# SoC_pwr_2.net
KiCad netlist of a schematic drawn in Altium Designer
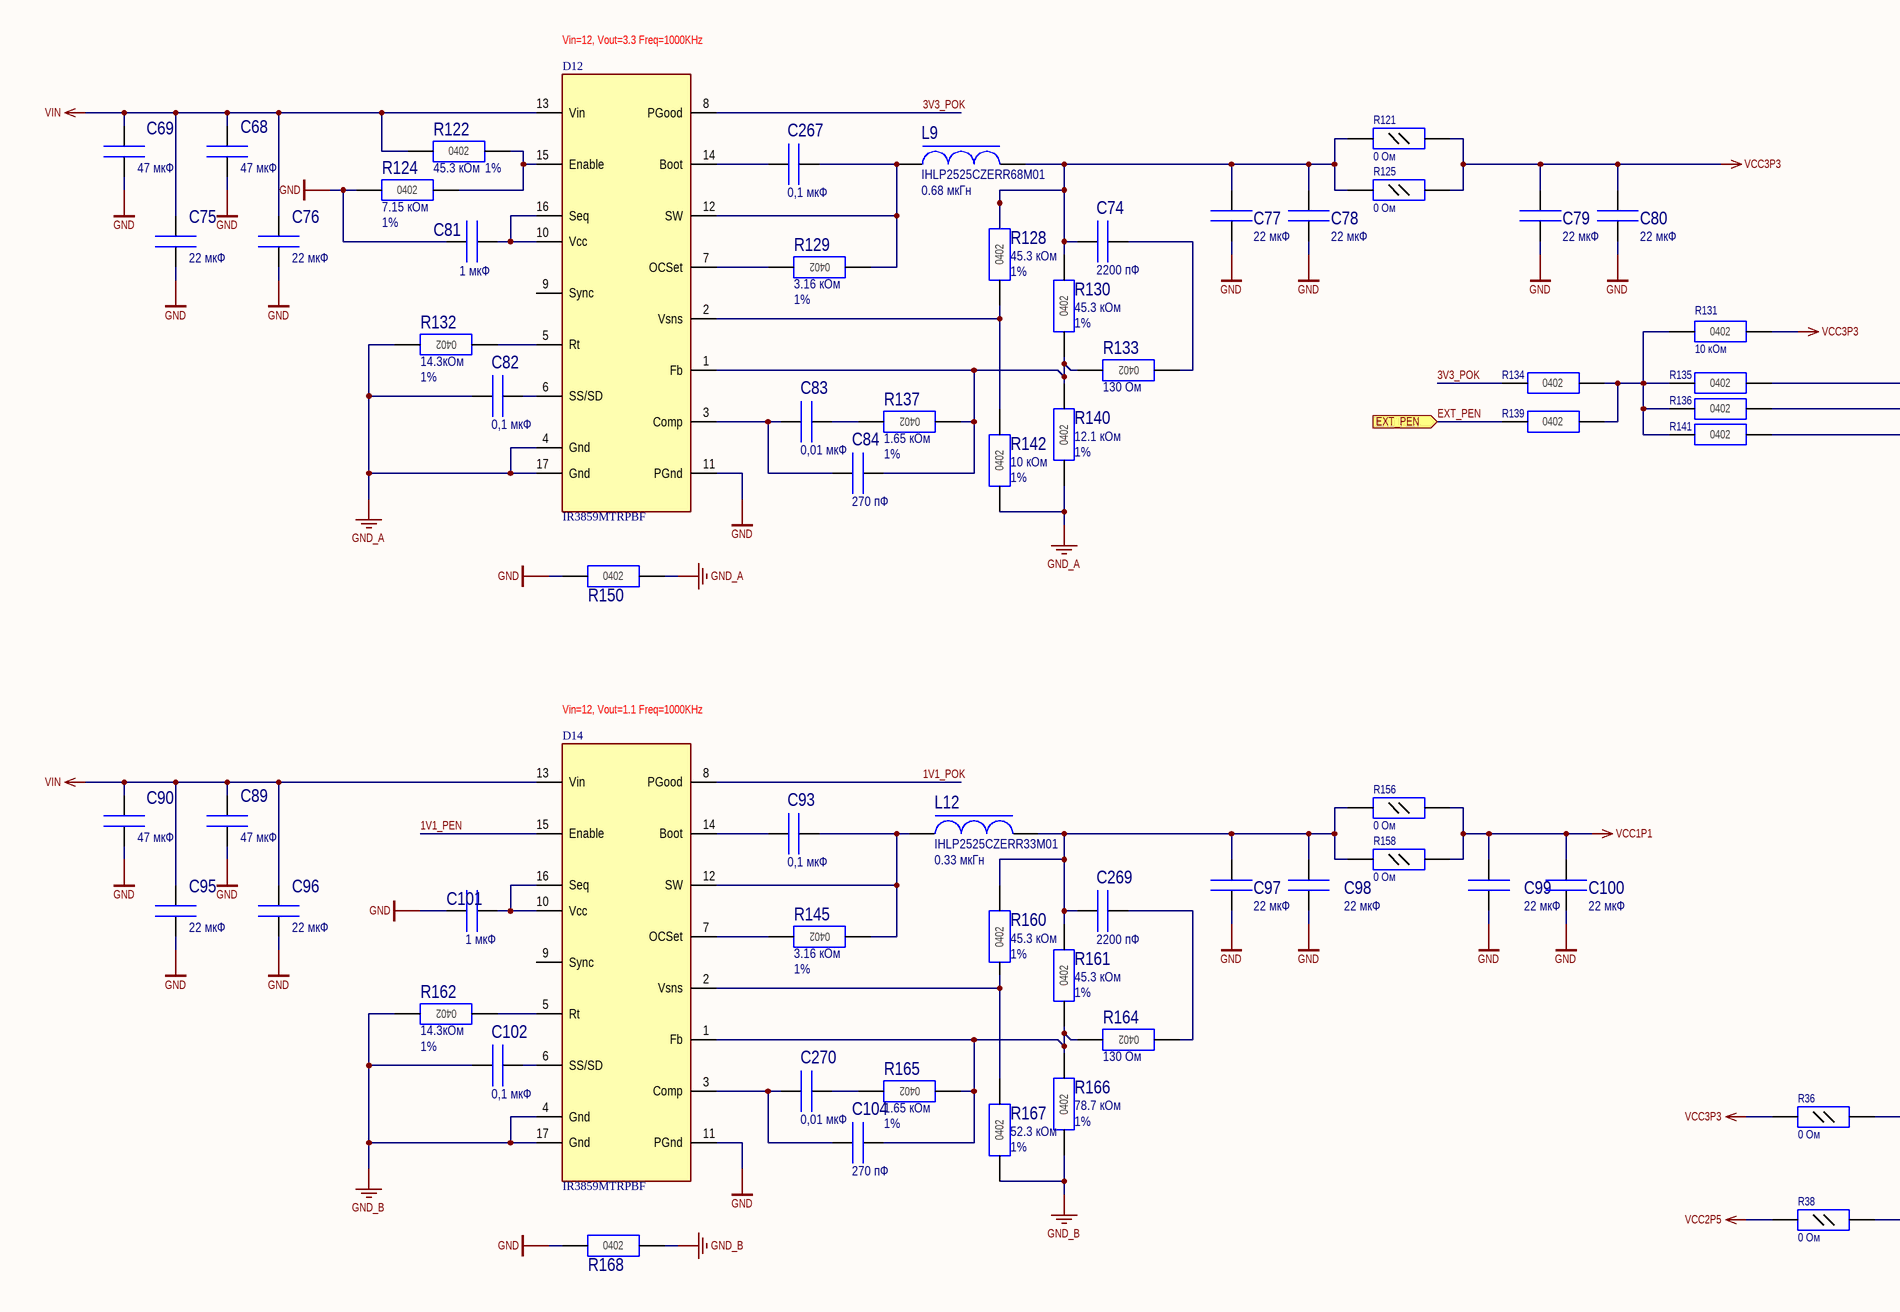
[diagram p0: SoC_pwr_2.SchDoc, left]
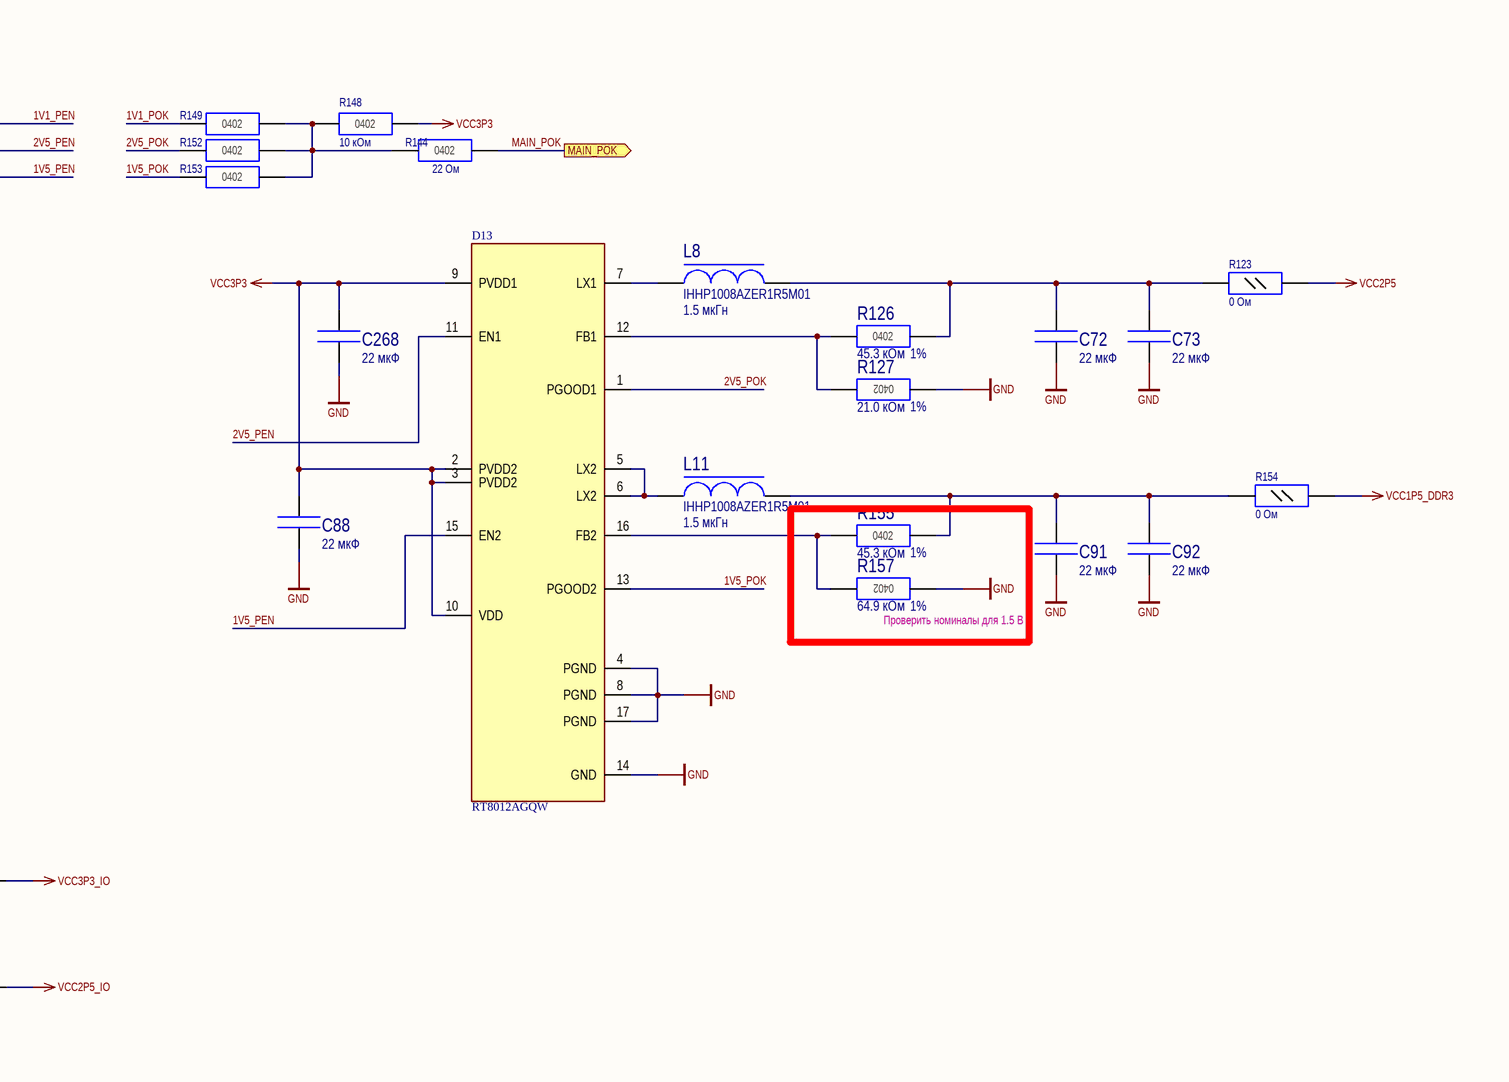
[diagram p1: SoC_pwr_2.SchDoc, right]

(export (version "E")
  (design (tool "Eeschema 10.0.6"))
  (components
    (comp (ref "C68")
      (value "47 мкФ")
      (footprint "CC0603")
      (description "Чип конденсатор керамический")
      (fields (field (name "Comment") "CC0603-X5R-47 мкФ-20%-6,3В"))
      (libsource (lib "Конденсаторы") (part "CC0603-X5R-#-20%-6,3В"))
    )
    (comp (ref "C69")
      (value "47 мкФ")
      (footprint "CC0603")
      (description "Чип конденсатор керамический")
      (fields (field (name "Comment") "CC0603-X5R-47 мкФ-20%-6,3В"))
      (libsource (lib "Конденсаторы") (part "CC0603-X5R-#-20%-6,3В"))
    )
    (comp (ref "C72")
      (value "22 мкФ")
      (footprint "CC0603")
      (description "Чип конденсатор керамический")
      (fields (field (name "Comment") "CC0603-X5R-22 мкФ-20%-6,3В"))
      (libsource (lib "Конденсаторы") (part "CC0603-X5R-#-20%-6,3В"))
    )
    (comp (ref "C73")
      (value "22 мкФ")
      (footprint "CC0603")
      (description "Чип конденсатор керамический")
      (fields (field (name "Comment") "CC0603-X5R-22 мкФ-20%-6,3В"))
      (libsource (lib "Конденсаторы") (part "CC0603-X5R-#-20%-6,3В"))
    )
    (comp (ref "C74")
      (value "2200 пФ")
      (footprint "CC0402(1005)")
      (description "Чип конденсатор керамический")
      (fields (field (name "Comment") "CC0402-X7R-2200 пФ-10%-16В"))
      (libsource (lib "Чип конденсаторы") (part "CC0402-X7R-#-20%-10В"))
    )
    (comp (ref "C75")
      (value "22 мкФ")
      (footprint "CC0603")
      (description "Чип конденсатор керамический")
      (fields (field (name "Comment") "CC0603-X5R-22 мкФ-20%-6,3В"))
      (libsource (lib "Конденсаторы") (part "CC0603-X5R-#-20%-6,3В"))
    )
    (comp (ref "C76")
      (value "22 мкФ")
      (footprint "CC0603")
      (description "Чип конденсатор керамический")
      (fields (field (name "Comment") "CC0603-X5R-22 мкФ-20%-6,3В"))
      (libsource (lib "Конденсаторы") (part "CC0603-X5R-#-20%-6,3В"))
    )
    (comp (ref "C77")
      (value "22 мкФ")
      (footprint "CC0603")
      (description "Чип конденсатор керамический")
      (fields (field (name "Comment") "CC0603-X5R-22 мкФ-20%-6,3В"))
      (libsource (lib "Конденсаторы") (part "CC0603-X5R-#-20%-6,3В"))
    )
    (comp (ref "C78")
      (value "22 мкФ")
      (footprint "CC0603")
      (description "Чип конденсатор керамический")
      (fields (field (name "Comment") "CC0603-X5R-22 мкФ-20%-6,3В"))
      (libsource (lib "Конденсаторы") (part "CC0603-X5R-#-20%-6,3В"))
    )
    (comp (ref "C79")
      (value "22 мкФ")
      (footprint "CC0603")
      (description "Чип конденсатор керамический")
      (fields (field (name "Comment") "CC0603-X5R-22 мкФ-20%-6,3В"))
      (libsource (lib "Конденсаторы") (part "CC0603-X5R-#-20%-6,3В"))
    )
    (comp (ref "C80")
      (value "22 мкФ")
      (footprint "CC0603")
      (description "Чип конденсатор керамический")
      (fields (field (name "Comment") "CC0603-X5R-22 мкФ-20%-6,3В"))
      (libsource (lib "Конденсаторы") (part "CC0603-X5R-#-20%-6,3В"))
    )
    (comp (ref "C81")
      (value "1 мкФ")
      (footprint "CC0603")
      (description "Чип конденсатор керамический")
      (fields (field (name "Comment") "CC0603-X5R-1 мкФ-10%-25В"))
      (libsource (lib "Конденсаторы") (part "CC0603-X5R-#-20%-6,3В"))
    )
    (comp (ref "C82")
      (value "0,1 мкФ")
      (footprint "CC0402(1005)")
      (description "Чип конденсатор керамический")
      (fields (field (name "Comment") "CC0402-X7R-0,1 мкФ-20%-10В"))
      (libsource (lib "Чип конденсаторы") (part "CC0402-X7R-#-20%-10В"))
    )
    (comp (ref "C83")
      (value "0,01 мкФ")
      (footprint "CC0402(1005)")
      (description "Чип конденсатор керамический")
      (fields (field (name "Comment") "CC0402-X7R-0,01 мкФ-10%-50В"))
      (libsource (lib "Чип конденсаторы") (part "CC0402-X7R-#-20%-10В"))
    )
    (comp (ref "C84")
      (value "270 пФ")
      (footprint "CC0402(1005)")
      (description "Чип конденсатор керамический")
      (fields (field (name "Comment") "CC0402-NP0-270 пФ-1%-50В"))
      (libsource (lib "Чип конденсаторы") (part "CC0402-X7R-#-20%-10В"))
    )
    (comp (ref "C88")
      (value "22 мкФ")
      (footprint "CC0603")
      (description "Чип конденсатор керамический")
      (fields (field (name "Comment") "CC0603-X5R-22 мкФ-20%-6,3В"))
      (libsource (lib "Конденсаторы") (part "CC0603-X5R-#-20%-6,3В"))
    )
    (comp (ref "C89")
      (value "47 мкФ")
      (footprint "CC0603")
      (description "Чип конденсатор керамический")
      (fields (field (name "Comment") "CC0603-X5R-47 мкФ-20%-6,3В"))
      (libsource (lib "Конденсаторы") (part "CC0603-X5R-#-20%-6,3В"))
    )
    (comp (ref "C90")
      (value "47 мкФ")
      (footprint "CC0603")
      (description "Чип конденсатор керамический")
      (fields (field (name "Comment") "CC0603-X5R-47 мкФ-20%-6,3В"))
      (libsource (lib "Конденсаторы") (part "CC0603-X5R-#-20%-6,3В"))
    )
    (comp (ref "C91")
      (value "22 мкФ")
      (footprint "CC0603")
      (description "Чип конденсатор керамический")
      (fields (field (name "Comment") "CC0603-X5R-22 мкФ-20%-6,3В"))
      (libsource (lib "Конденсаторы") (part "CC0603-X5R-#-20%-6,3В"))
    )
    (comp (ref "C92")
      (value "22 мкФ")
      (footprint "CC0603")
      (description "Чип конденсатор керамический")
      (fields (field (name "Comment") "CC0603-X5R-22 мкФ-20%-6,3В"))
      (libsource (lib "Конденсаторы") (part "CC0603-X5R-#-20%-6,3В"))
    )
    (comp (ref "C93")
      (value "0,1 мкФ")
      (footprint "CC0402(1005)")
      (description "Чип конденсатор керамический")
      (fields (field (name "Comment") "CC0402-X7R-0,1 мкФ-20%-10В"))
      (libsource (lib "Чип конденсаторы") (part "CC0402-X7R-#-20%-10В"))
    )
    (comp (ref "C95")
      (value "22 мкФ")
      (footprint "CC0603")
      (description "Чип конденсатор керамический")
      (fields (field (name "Comment") "CC0603-X5R-22 мкФ-20%-6,3В"))
      (libsource (lib "Конденсаторы") (part "CC0603-X5R-#-20%-6,3В"))
    )
    (comp (ref "C96")
      (value "22 мкФ")
      (footprint "CC0603")
      (description "Чип конденсатор керамический")
      (fields (field (name "Comment") "CC0603-X5R-22 мкФ-20%-6,3В"))
      (libsource (lib "Конденсаторы") (part "CC0603-X5R-#-20%-6,3В"))
    )
    (comp (ref "C97")
      (value "22 мкФ")
      (footprint "CC0603")
      (description "Чип конденсатор керамический")
      (fields (field (name "Comment") "CC0603-X5R-22 мкФ-20%-6,3В"))
      (libsource (lib "Конденсаторы") (part "CC0603-X5R-#-20%-6,3В"))
    )
    (comp (ref "C98")
      (value "22 мкФ")
      (footprint "CC0603")
      (description "Чип конденсатор керамический")
      (fields (field (name "Comment") "CC0603-X5R-22 мкФ-20%-6,3В"))
      (libsource (lib "Конденсаторы") (part "CC0603-X5R-#-20%-6,3В"))
    )
    (comp (ref "C99")
      (value "22 мкФ")
      (footprint "CC0603")
      (description "Чип конденсатор керамический")
      (fields (field (name "Comment") "CC0603-X5R-22 мкФ-20%-6,3В"))
      (libsource (lib "Конденсаторы") (part "CC0603-X5R-#-20%-6,3В"))
    )
    (comp (ref "C100")
      (value "22 мкФ")
      (footprint "CC0603")
      (description "Чип конденсатор керамический")
      (fields (field (name "Comment") "CC0603-X5R-22 мкФ-20%-6,3В"))
      (libsource (lib "Конденсаторы") (part "CC0603-X5R-#-20%-6,3В"))
    )
    (comp (ref "C101")
      (value "1 мкФ")
      (footprint "CC0603")
      (description "Чип конденсатор керамический")
      (fields (field (name "Comment") "CC0603-X5R-1 мкФ-10%-25В"))
      (libsource (lib "Конденсаторы") (part "CC0603-X5R-#-20%-6,3В"))
    )
    (comp (ref "C102")
      (value "0,1 мкФ")
      (footprint "CC0402(1005)")
      (description "Чип конденсатор керамический")
      (fields (field (name "Comment") "CC0402-X7R-0,1 мкФ-20%-10В"))
      (libsource (lib "Чип конденсаторы") (part "CC0402-X7R-#-20%-10В"))
    )
    (comp (ref "C104")
      (value "270 пФ")
      (footprint "CC0402(1005)")
      (description "Чип конденсатор керамический")
      (fields (field (name "Comment") "CC0402-NP0-270 пФ-1%-50В"))
      (libsource (lib "Чип конденсаторы") (part "CC0402-X7R-#-20%-10В"))
    )
    (comp (ref "C267")
      (value "0,1 мкФ")
      (footprint "CC0402(1005)")
      (description "Чип конденсатор керамический")
      (fields (field (name "Comment") "CC0402-X7R-0,1 мкФ-20%-10В"))
      (libsource (lib "Чип конденсаторы") (part "CC0402-X7R-#-20%-10В"))
    )
    (comp (ref "C268")
      (value "22 мкФ")
      (footprint "CC0603")
      (description "Чип конденсатор керамический")
      (fields (field (name "Comment") "CC0603-X5R-22 мкФ-20%-6,3В"))
      (libsource (lib "Конденсаторы") (part "CC0603-X5R-#-20%-6,3В"))
    )
    (comp (ref "C269")
      (value "2200 пФ")
      (footprint "CC0402(1005)")
      (description "Чип конденсатор керамический")
      (fields (field (name "Comment") "CC0402-X7R-2200 пФ-10%-16В"))
      (libsource (lib "Чип конденсаторы") (part "CC0402-X7R-#-20%-10В"))
    )
    (comp (ref "C270")
      (value "0,01 мкФ")
      (footprint "CC0402(1005)")
      (description "Чип конденсатор керамический")
      (fields (field (name "Comment") "CC0402-X7R-0,01 мкФ-10%-50В"))
      (libsource (lib "Чип конденсаторы") (part "CC0402-X7R-#-20%-10В"))
    )
    (comp (ref "D12")
      (value "IR3859MTRPBF")
      (footprint "IR3859")
      (description "IC REG BUCK ADJ 9A SYNC 17PQFN")
      (libsource (lib "SD_IC") (part "IR3859MPbF"))
    )
    (comp (ref "D13")
      (value "RT8012AGQW")
      (footprint "RT8012AGQW")
      (libsource (lib "SD_IC") (part "RT8012AGQW"))
    )
    (comp (ref "D14")
      (value "IR3859MTRPBF")
      (footprint "IR3859")
      (description "IC REG BUCK ADJ 9A SYNC 17PQFN")
      (libsource (lib "SD_IC") (part "IR3859MPbF"))
    )
    (comp (ref "L8")
      (value "IHHP1008AZER1R5M01")
      (footprint "INDC2720X12L")
      (description "FIXED IND 1.5UH 2.4A 96 MOHM SMD")
      (fields (field (name "ALTIUM_VALUE") "1.5 мкГн"))
      (libsource (lib "SD_IC") (part "L_VISH_IIHHP1008ABE_1"))
    )
    (comp (ref "L9")
      (value "IHLP2525CZERR68M01")
      (footprint "IHPL2525")
      (description "FIXED IND 680NH 15.5A 5.5 MOHM")
      (fields (field (name "ALTIUM_VALUE") "0.68 мкГн"))
      (libsource (lib "SD_IC") (part "L_VISH_IHLP2525CZERR68M01"))
    )
    (comp (ref "L11")
      (value "IHHP1008AZER1R5M01")
      (footprint "INDC2720X12L")
      (description "FIXED IND 1.5UH 2.4A 96 MOHM SMD")
      (fields (field (name "ALTIUM_VALUE") "1.5 мкГн"))
      (libsource (lib "SD_IC") (part "L_VISH_IIHHP1008ABE_1"))
    )
    (comp (ref "L12")
      (value "IHLP2525CZERR33M01")
      (footprint "IHPL2525")
      (description "FIXED IND 680NH 15.5A 5.5 MOHM")
      (fields (field (name "ALTIUM_VALUE") "0.33 мкГн"))
      (libsource (lib "SD_IC") (part "L_VISH_IHLP2525CZERR68M01"))
    )
    (comp (ref "R36")
      (value "0 Ом")
      (footprint "CR0805")
      (description "Чип резистор")
      (fields (field (name "Comment") "CR0805-0 Ом-±5%"))
      (libsource (lib "Резисторы") (part "CR0805-#-±5%"))
    )
    (comp (ref "R38")
      (value "0 Ом")
      (footprint "CR0805")
      (description "Чип резистор")
      (fields (field (name "Comment") "CR0805-0 Ом-±5%"))
      (libsource (lib "Резисторы") (part "CR0805-#-±5%"))
    )
    (comp (ref "R121")
      (value "0 Ом")
      (footprint "CR0805")
      (description "Чип резистор")
      (fields (field (name "Comment") "CR0805-0 Ом-±5%"))
      (libsource (lib "Резисторы") (part "CR0805-#-±5%"))
    )
    (comp (ref "R122")
      (value "45.3 кОм")
      (footprint "CR0402(1005)")
      (description "Чип резистор")
      (fields (field (name "TOLERANCE") "1%") (field (name "Comment") "CR0402-45.3 кОм-±1%"))
      (libsource (lib "") (part "CR0402-#-±1%_2"))
    )
    (comp (ref "R123")
      (value "0 Ом")
      (footprint "CR0805")
      (description "Чип резистор")
      (fields (field (name "Comment") "CR0805-0 Ом-±5%"))
      (libsource (lib "Резисторы") (part "CR0805-#-±5%"))
    )
    (comp (ref "R124")
      (value "7.15 кОм")
      (footprint "CR0402(1005)")
      (description "Чип резистор")
      (fields (field (name "TOLERANCE") "1%") (field (name "Comment") "CR0402-7.15 кОм-±1%"))
      (libsource (lib "") (part "CR0402-#-±1%_2"))
    )
    (comp (ref "R125")
      (value "0 Ом")
      (footprint "CR0805")
      (description "Чип резистор")
      (fields (field (name "Comment") "CR0805-0 Ом-±5%"))
      (libsource (lib "Резисторы") (part "CR0805-#-±5%"))
    )
    (comp (ref "R126")
      (value "45.3 кОм")
      (footprint "CR0402(1005)")
      (description "Чип резистор")
      (fields (field (name "TOLERANCE") "1%") (field (name "Comment") "CR0402-45.3 кОм-±1%"))
      (libsource (lib "") (part "CR0402-#-±1%_2"))
    )
    (comp (ref "R127")
      (value "21.0 кОм")
      (footprint "CR0402(1005)")
      (description "Чип резистор")
      (fields (field (name "TOLERANCE") "1%") (field (name "Comment") "CR0402-21.0 кОм-±1%"))
      (libsource (lib "Чип резисторы") (part "CR0402-#-±1%"))
    )
    (comp (ref "R128")
      (value "45.3 кОм")
      (footprint "CR0402(1005)")
      (description "Чип резистор")
      (fields (field (name "TOLERANCE") "1%") (field (name "Comment") "CR0402-45.3 кОм-±1%"))
      (libsource (lib "") (part "CR0402-#-±1%_1"))
    )
    (comp (ref "R129")
      (value "3.16 кОм")
      (footprint "CR0402(1005)")
      (description "Чип резистор")
      (fields (field (name "TOLERANCE") "1%") (field (name "Comment") "CR0402-3.16 кОм-±1%"))
      (libsource (lib "Чип резисторы") (part "CR0402-#-±1%"))
    )
    (comp (ref "R130")
      (value "45.3 кОм")
      (footprint "CR0402(1005)")
      (description "Чип резистор")
      (fields (field (name "TOLERANCE") "1%") (field (name "Comment") "CR0402-45.3 кОм-±1%"))
      (libsource (lib "") (part "CR0402-#-±1%_1"))
    )
    (comp (ref "R131")
      (value "10 кОм")
      (footprint "CR0402(1005)")
      (description "Чип резистор")
      (fields (field (name "TOLERANCE") "5%") (field (name "Comment") "CR0402-10 кОм-±5%"))
      (libsource (lib "Резисторы") (part "CR0402-#-±5%"))
    )
    (comp (ref "R132")
      (value "14.3кОм")
      (footprint "CR0402(1005)")
      (description "Чип резистор")
      (fields (field (name "TOLERANCE") "1%") (field (name "Comment") "CR0402-14.3кОм-±1%"))
      (libsource (lib "Чип резисторы") (part "CR0402-#-±1%"))
    )
    (comp (ref "R133")
      (value "130 Ом")
      (footprint "CR0402(1005)")
      (description "Чип резистор")
      (fields (field (name "Comment") "CR0402-130 Ом-±1%"))
      (libsource (lib "Чип резисторы") (part "CR0402-#-±1%"))
    )
    (comp (ref "R134")
      (value "CR0402-0 Ом-±5%")
      (footprint "CR0402(1005)")
      (description "Чип резистор")
      (fields (field (name "TOLERANCE") "5%"))
      (libsource (lib "Резисторы") (part "CR0402-#-±5%"))
    )
    (comp (ref "R135")
      (value "CR0402-0 Ом-±5%")
      (footprint "CR0402(1005)")
      (description "Чип резистор")
      (fields (field (name "TOLERANCE") "5%"))
      (libsource (lib "Резисторы") (part "CR0402-#-±5%"))
    )
    (comp (ref "R136")
      (value "CR0402-0 Ом-±5%")
      (footprint "CR0402(1005)")
      (description "Чип резистор")
      (fields (field (name "TOLERANCE") "5%"))
      (libsource (lib "Резисторы") (part "CR0402-#-±5%"))
    )
    (comp (ref "R137")
      (value "1.65 кОм")
      (footprint "CR0402(1005)")
      (description "Чип резистор")
      (fields (field (name "TOLERANCE") "1%") (field (name "Comment") "CR0402-1.65 кОм-±1%"))
      (libsource (lib "Чип резисторы") (part "CR0402-#-±1%"))
    )
    (comp (ref "R139")
      (value "CR0402-0 Ом-±5%")
      (footprint "CR0402(1005)")
      (description "Чип резистор")
      (fields (field (name "TOLERANCE") "5%"))
      (libsource (lib "Резисторы") (part "CR0402-#-±5%"))
    )
    (comp (ref "R140")
      (value "12.1 кОм")
      (footprint "CR0402(1005)")
      (description "Чип резистор")
      (fields (field (name "TOLERANCE") "1%") (field (name "Comment") "CR0402-12.1 кОм-±1%"))
      (libsource (lib "") (part "CR0402-#-±1%_1"))
    )
    (comp (ref "R141")
      (value "CR0402-0 Ом-±5%")
      (footprint "CR0402(1005)")
      (description "Чип резистор")
      (fields (field (name "TOLERANCE") "5%"))
      (libsource (lib "Резисторы") (part "CR0402-#-±5%"))
    )
    (comp (ref "R142")
      (value "10 кОм")
      (footprint "CR0402(1005)")
      (description "Чип резистор")
      (fields (field (name "TOLERANCE") "1%") (field (name "Comment") "CR0402-10 кОм-±1%"))
      (libsource (lib "") (part "CR0402-#-±1%_1"))
    )
    (comp (ref "R144")
      (value "22 Ом")
      (footprint "CR0402(1005)")
      (description "Чип резистор")
      (fields (field (name "TOLERANCE") "5%") (field (name "Comment") "CR0402-22 Ом-±5%"))
      (libsource (lib "Чип резисторы") (part "CR0402-#-±5%"))
    )
    (comp (ref "R145")
      (value "3.16 кОм")
      (footprint "CR0402(1005)")
      (description "Чип резистор")
      (fields (field (name "TOLERANCE") "1%") (field (name "Comment") "CR0402-3.16 кОм-±1%"))
      (libsource (lib "Чип резисторы") (part "CR0402-#-±1%"))
    )
    (comp (ref "R148")
      (value "10 кОм")
      (footprint "CR0402(1005)")
      (description "Чип резистор")
      (fields (field (name "TOLERANCE") "5%") (field (name "Comment") "CR0402-10 кОм-±5%"))
      (libsource (lib "Резисторы") (part "CR0402-#-±5%"))
    )
    (comp (ref "R149")
      (value "CR0402-0 Ом-±5%")
      (footprint "CR0402(1005)")
      (description "Чип резистор")
      (fields (field (name "TOLERANCE") "5%"))
      (libsource (lib "Резисторы") (part "CR0402-#-±5%"))
    )
    (comp (ref "R150")
      (value "CR0402-0 Ом-±5%")
      (footprint "CR0402(1005)")
      (description "Чип резистор")
      (fields (field (name "TOLERANCE") "5%"))
      (libsource (lib "Резисторы") (part "CR0402-#-±5%"))
    )
    (comp (ref "R152")
      (value "CR0402-0 Ом-±5%")
      (footprint "CR0402(1005)")
      (description "Чип резистор")
      (fields (field (name "TOLERANCE") "5%"))
      (libsource (lib "Резисторы") (part "CR0402-#-±5%"))
    )
    (comp (ref "R153")
      (value "CR0402-0 Ом-±5%")
      (footprint "CR0402(1005)")
      (description "Чип резистор")
      (fields (field (name "TOLERANCE") "5%"))
      (libsource (lib "Резисторы") (part "CR0402-#-±5%"))
    )
    (comp (ref "R154")
      (value "0 Ом")
      (footprint "CR0805")
      (description "Чип резистор")
      (fields (field (name "Comment") "CR0805-0 Ом-±5%"))
      (libsource (lib "Резисторы") (part "CR0805-#-±5%"))
    )
    (comp (ref "R155")
      (value "45.3 кОм")
      (footprint "CR0402(1005)")
      (description "Чип резистор")
      (fields (field (name "TOLERANCE") "1%") (field (name "Comment") "CR0402-45.3 кОм-±1%"))
      (libsource (lib "") (part "CR0402-#-±1%_2"))
    )
    (comp (ref "R156")
      (value "0 Ом")
      (footprint "CR0805")
      (description "Чип резистор")
      (fields (field (name "Comment") "CR0805-0 Ом-±5%"))
      (libsource (lib "Резисторы") (part "CR0805-#-±5%"))
    )
    (comp (ref "R157")
      (value "64.9 кОм")
      (footprint "CR0402(1005)")
      (description "Чип резистор")
      (fields (field (name "TOLERANCE") "1%") (field (name "Comment") "CR0402-64.9 кОм-±1%"))
      (libsource (lib "Чип резисторы") (part "CR0402-#-±1%"))
    )
    (comp (ref "R158")
      (value "0 Ом")
      (footprint "CR0805")
      (description "Чип резистор")
      (fields (field (name "Comment") "CR0805-0 Ом-±5%"))
      (libsource (lib "Резисторы") (part "CR0805-#-±5%"))
    )
    (comp (ref "R160")
      (value "45.3 кОм")
      (footprint "CR0402(1005)")
      (description "Чип резистор")
      (fields (field (name "TOLERANCE") "1%") (field (name "Comment") "CR0402-45.3 кОм-±1%"))
      (libsource (lib "") (part "CR0402-#-±1%_1"))
    )
    (comp (ref "R161")
      (value "45.3 кОм")
      (footprint "CR0402(1005)")
      (description "Чип резистор")
      (fields (field (name "TOLERANCE") "1%") (field (name "Comment") "CR0402-45.3 кОм-±1%"))
      (libsource (lib "") (part "CR0402-#-±1%_1"))
    )
    (comp (ref "R162")
      (value "14.3кОм")
      (footprint "CR0402(1005)")
      (description "Чип резистор")
      (fields (field (name "TOLERANCE") "1%") (field (name "Comment") "CR0402-14.3кОм-±1%"))
      (libsource (lib "Чип резисторы") (part "CR0402-#-±1%"))
    )
    (comp (ref "R164")
      (value "130 Ом")
      (footprint "CR0402(1005)")
      (description "Чип резистор")
      (fields (field (name "Comment") "CR0402-130 Ом-±1%"))
      (libsource (lib "Чип резисторы") (part "CR0402-#-±1%"))
    )
    (comp (ref "R165")
      (value "1.65 кОм")
      (footprint "CR0402(1005)")
      (description "Чип резистор")
      (fields (field (name "TOLERANCE") "1%") (field (name "Comment") "CR0402-1.65 кОм-±1%"))
      (libsource (lib "Чип резисторы") (part "CR0402-#-±1%"))
    )
    (comp (ref "R166")
      (value "78.7 кОм")
      (footprint "CR0402(1005)")
      (description "Чип резистор")
      (fields (field (name "TOLERANCE") "1%") (field (name "Comment") "CR0402-78.7 кОм-±1%"))
      (libsource (lib "") (part "CR0402-#-±1%_1"))
    )
    (comp (ref "R167")
      (value "52.3 кОм")
      (footprint "CR0402(1005)")
      (description "Чип резистор")
      (fields (field (name "TOLERANCE") "1%") (field (name "Comment") "CR0402-52.3 кОм-±1%"))
      (libsource (lib "") (part "CR0402-#-±1%_1"))
    )
    (comp (ref "R168")
      (value "CR0402-0 Ом-±5%")
      (footprint "CR0402(1005)")
      (description "Чип резистор")
      (fields (field (name "TOLERANCE") "5%"))
      (libsource (lib "Резисторы") (part "CR0402-#-±5%"))
    )
  )
  (nets
    (net (code "1") (name "/1V1_PEN") (class "Default")
      (node (ref "D14") (pin "15") (pinfunction "Enable_15") (pintype "passive"))
      (node (ref "R135") (pin "2") (pinfunction "-_2") (pintype "passive"))
    )
    (net (code "2") (name "/1V1_POK") (class "Default")
      (node (ref "D14") (pin "8") (pinfunction "PGood_8") (pintype "passive"))
      (node (ref "R149") (pin "1") (pinfunction "+_1") (pintype "passive"))
    )
    (net (code "3") (name "/1V5_PEN") (class "Default")
      (node (ref "D13") (pin "15") (pinfunction "EN2_15") (pintype "passive"))
      (node (ref "R141") (pin "2") (pinfunction "-_2") (pintype "passive"))
    )
    (net (code "4") (name "/1V5_POK") (class "Default")
      (node (ref "D13") (pin "13") (pinfunction "PGOOD2_13") (pintype "passive"))
      (node (ref "R153") (pin "1") (pinfunction "+_1") (pintype "passive"))
    )
    (net (code "5") (name "/2V5_PEN") (class "Default")
      (node (ref "D13") (pin "11") (pinfunction "EN1_11") (pintype "passive"))
      (node (ref "R136") (pin "2") (pinfunction "-_2") (pintype "passive"))
    )
    (net (code "6") (name "/2V5_POK") (class "Default")
      (node (ref "D13") (pin "1") (pinfunction "PGOOD1_1") (pintype "passive"))
      (node (ref "R152") (pin "1") (pinfunction "+_1") (pintype "passive"))
    )
    (net (code "7") (name "/3V3_POK") (class "Default")
      (node (ref "D12") (pin "8") (pinfunction "PGood_8") (pintype "passive"))
      (node (ref "R134") (pin "1") (pinfunction "+_1") (pintype "passive"))
    )
    (net (code "8") (name "/EXT_PEN") (class "Default")
      (node (ref "R139") (pin "1") (pinfunction "+_1") (pintype "passive"))
    )
    (net (code "9") (name "/MAIN_POK") (class "Default")
      (node (ref "R144") (pin "2") (pinfunction "-_2") (pintype "passive"))
    )
    (net (code "10") (name "GND") (class "Default")
      (node (ref "C100") (pin "2") (pinfunction "-_2") (pintype "passive"))
      (node (ref "C101") (pin "1") (pinfunction "+_1") (pintype "passive"))
      (node (ref "C268") (pin "2") (pinfunction "-_2") (pintype "passive"))
      (node (ref "C68") (pin "2") (pinfunction "-_2") (pintype "passive"))
      (node (ref "C69") (pin "2") (pinfunction "-_2") (pintype "passive"))
      (node (ref "C72") (pin "2") (pinfunction "-_2") (pintype "passive"))
      (node (ref "C73") (pin "2") (pinfunction "-_2") (pintype "passive"))
      (node (ref "C75") (pin "2") (pinfunction "-_2") (pintype "passive"))
      (node (ref "C76") (pin "2") (pinfunction "-_2") (pintype "passive"))
      (node (ref "C77") (pin "2") (pinfunction "-_2") (pintype "passive"))
      (node (ref "C78") (pin "2") (pinfunction "-_2") (pintype "passive"))
      (node (ref "C79") (pin "2") (pinfunction "-_2") (pintype "passive"))
      (node (ref "C80") (pin "2") (pinfunction "-_2") (pintype "passive"))
      (node (ref "C81") (pin "1") (pinfunction "+_1") (pintype "passive"))
      (node (ref "C88") (pin "2") (pinfunction "-_2") (pintype "passive"))
      (node (ref "C89") (pin "2") (pinfunction "-_2") (pintype "passive"))
      (node (ref "C90") (pin "2") (pinfunction "-_2") (pintype "passive"))
      (node (ref "C91") (pin "2") (pinfunction "-_2") (pintype "passive"))
      (node (ref "C92") (pin "2") (pinfunction "-_2") (pintype "passive"))
      (node (ref "C95") (pin "2") (pinfunction "-_2") (pintype "passive"))
      (node (ref "C96") (pin "2") (pinfunction "-_2") (pintype "passive"))
      (node (ref "C97") (pin "2") (pinfunction "-_2") (pintype "passive"))
      (node (ref "C98") (pin "2") (pinfunction "-_2") (pintype "passive"))
      (node (ref "C99") (pin "2") (pinfunction "-_2") (pintype "passive"))
      (node (ref "D12") (pin "11") (pinfunction "PGnd_11") (pintype "passive"))
      (node (ref "D13") (pin "14") (pinfunction "GND_14") (pintype "passive"))
      (node (ref "D13") (pin "17") (pinfunction "PGND_17") (pintype "passive"))
      (node (ref "D13") (pin "4") (pinfunction "PGND_4") (pintype "passive"))
      (node (ref "D13") (pin "8") (pinfunction "PGND_8") (pintype "passive"))
      (node (ref "D14") (pin "11") (pinfunction "PGnd_11") (pintype "passive"))
      (node (ref "R124") (pin "1") (pinfunction "+_1") (pintype "passive"))
      (node (ref "R127") (pin "1") (pinfunction "+_1") (pintype "passive"))
      (node (ref "R150") (pin "1") (pinfunction "+_1") (pintype "passive"))
      (node (ref "R157") (pin "1") (pinfunction "+_1") (pintype "passive"))
      (node (ref "R168") (pin "1") (pinfunction "+_1") (pintype "passive"))
    )
    (net (code "11") (name "GND_A") (class "Default")
      (node (ref "C82") (pin "1") (pinfunction "+_1") (pintype "passive"))
      (node (ref "D12") (pin "17") (pinfunction "Gnd_17") (pintype "passive"))
      (node (ref "D12") (pin "4") (pinfunction "Gnd_4") (pintype "passive"))
      (node (ref "R132") (pin "2") (pinfunction "-_2") (pintype "passive"))
      (node (ref "R140") (pin "1") (pinfunction "+_1") (pintype "passive"))
      (node (ref "R142") (pin "1") (pinfunction "+_1") (pintype "passive"))
      (node (ref "R150") (pin "2") (pinfunction "-_2") (pintype "passive"))
    )
    (net (code "12") (name "GND_B") (class "Default")
      (node (ref "C102") (pin "1") (pinfunction "+_1") (pintype "passive"))
      (node (ref "D14") (pin "17") (pinfunction "Gnd_17") (pintype "passive"))
      (node (ref "D14") (pin "4") (pinfunction "Gnd_4") (pintype "passive"))
      (node (ref "R162") (pin "2") (pinfunction "-_2") (pintype "passive"))
      (node (ref "R166") (pin "1") (pinfunction "+_1") (pintype "passive"))
      (node (ref "R167") (pin "1") (pinfunction "+_1") (pintype "passive"))
      (node (ref "R168") (pin "2") (pinfunction "-_2") (pintype "passive"))
    )
    (net (code "13") (name "Net-(C72-+)") (class "Default")
      (node (ref "C72") (pin "1") (pinfunction "+_1") (pintype "passive"))
      (node (ref "C73") (pin "1") (pinfunction "+_1") (pintype "passive"))
      (node (ref "L8") (pin "2") (pinfunction "2_2") (pintype "passive"))
      (node (ref "R123") (pin "1") (pinfunction "+_1") (pintype "passive"))
      (node (ref "R126") (pin "2") (pinfunction "-_2") (pintype "passive"))
    )
    (net (code "14") (name "Net-(C74-+)") (class "Default")
      (node (ref "C74") (pin "1") (pinfunction "+_1") (pintype "passive"))
      (node (ref "R133") (pin "1") (pinfunction "+_1") (pintype "passive"))
    )
    (net (code "15") (name "Net-(C74--)") (class "Default")
      (node (ref "C74") (pin "2") (pinfunction "-_2") (pintype "passive"))
      (node (ref "C77") (pin "1") (pinfunction "+_1") (pintype "passive"))
      (node (ref "C78") (pin "1") (pinfunction "+_1") (pintype "passive"))
      (node (ref "L9") (pin "2") (pinfunction "2_2") (pintype "passive"))
      (node (ref "R121") (pin "1") (pinfunction "+_1") (pintype "passive"))
      (node (ref "R125") (pin "1") (pinfunction "+_1") (pintype "passive"))
      (node (ref "R128") (pin "2") (pinfunction "-_2") (pintype "passive"))
      (node (ref "R130") (pin "2") (pinfunction "-_2") (pintype "passive"))
    )
    (net (code "16") (name "Net-(C81--)") (class "Default")
      (node (ref "C81") (pin "2") (pinfunction "-_2") (pintype "passive"))
      (node (ref "D12") (pin "10") (pinfunction "Vcc_10") (pintype "passive"))
      (node (ref "D12") (pin "16") (pinfunction "Seq_16") (pintype "passive"))
    )
    (net (code "17") (name "Net-(C82--)") (class "Default")
      (node (ref "C82") (pin "2") (pinfunction "-_2") (pintype "passive"))
      (node (ref "D12") (pin "6") (pinfunction "SS/SD_6") (pintype "passive"))
    )
    (net (code "18") (name "Net-(C83-+)") (class "Default")
      (node (ref "C83") (pin "1") (pinfunction "+_1") (pintype "passive"))
      (node (ref "C84") (pin "2") (pinfunction "-_2") (pintype "passive"))
      (node (ref "D12") (pin "3") (pinfunction "Comp_3") (pintype "passive"))
    )
    (net (code "19") (name "Net-(C83--)") (class "Default")
      (node (ref "C83") (pin "2") (pinfunction "-_2") (pintype "passive"))
      (node (ref "R137") (pin "2") (pinfunction "-_2") (pintype "passive"))
    )
    (net (code "20") (name "Net-(C84-+)") (class "Default")
      (node (ref "C84") (pin "1") (pinfunction "+_1") (pintype "passive"))
      (node (ref "D12") (pin "1") (pinfunction "Fb_1") (pintype "passive"))
      (node (ref "R130") (pin "1") (pinfunction "+_1") (pintype "passive"))
      (node (ref "R133") (pin "2") (pinfunction "-_2") (pintype "passive"))
      (node (ref "R137") (pin "1") (pinfunction "+_1") (pintype "passive"))
      (node (ref "R140") (pin "2") (pinfunction "-_2") (pintype "passive"))
    )
    (net (code "21") (name "Net-(C91-+)") (class "Default")
      (node (ref "C91") (pin "1") (pinfunction "+_1") (pintype "passive"))
      (node (ref "C92") (pin "1") (pinfunction "+_1") (pintype "passive"))
      (node (ref "L11") (pin "2") (pinfunction "2_2") (pintype "passive"))
      (node (ref "R154") (pin "1") (pinfunction "+_1") (pintype "passive"))
      (node (ref "R155") (pin "2") (pinfunction "-_2") (pintype "passive"))
    )
    (net (code "22") (name "Net-(C93-+)") (class "Default")
      (node (ref "C93") (pin "1") (pinfunction "+_1") (pintype "passive"))
      (node (ref "D14") (pin "14") (pinfunction "Boot_14") (pintype "passive"))
    )
    (net (code "23") (name "Net-(C93--)") (class "Default")
      (node (ref "C93") (pin "2") (pinfunction "-_2") (pintype "passive"))
      (node (ref "D14") (pin "12") (pinfunction "SW_12") (pintype "passive"))
      (node (ref "L12") (pin "1") (pinfunction "1_1") (pintype "passive"))
      (node (ref "R145") (pin "1") (pinfunction "+_1") (pintype "passive"))
    )
    (net (code "24") (name "Net-(C101--)") (class "Default")
      (node (ref "C101") (pin "2") (pinfunction "-_2") (pintype "passive"))
      (node (ref "D14") (pin "10") (pinfunction "Vcc_10") (pintype "passive"))
      (node (ref "D14") (pin "16") (pinfunction "Seq_16") (pintype "passive"))
    )
    (net (code "25") (name "Net-(C102--)") (class "Default")
      (node (ref "C102") (pin "2") (pinfunction "-_2") (pintype "passive"))
      (node (ref "D14") (pin "6") (pinfunction "SS/SD_6") (pintype "passive"))
    )
    (net (code "26") (name "Net-(C104-+)") (class "Default")
      (node (ref "C104") (pin "1") (pinfunction "+_1") (pintype "passive"))
      (node (ref "D14") (pin "1") (pinfunction "Fb_1") (pintype "passive"))
      (node (ref "R161") (pin "1") (pinfunction "+_1") (pintype "passive"))
      (node (ref "R164") (pin "2") (pinfunction "-_2") (pintype "passive"))
      (node (ref "R165") (pin "1") (pinfunction "+_1") (pintype "passive"))
      (node (ref "R166") (pin "2") (pinfunction "-_2") (pintype "passive"))
    )
    (net (code "27") (name "Net-(C104--)") (class "Default")
      (node (ref "C104") (pin "2") (pinfunction "-_2") (pintype "passive"))
      (node (ref "C270") (pin "1") (pinfunction "+_1") (pintype "passive"))
      (node (ref "D14") (pin "3") (pinfunction "Comp_3") (pintype "passive"))
    )
    (net (code "28") (name "Net-(C267-+)") (class "Default")
      (node (ref "C267") (pin "1") (pinfunction "+_1") (pintype "passive"))
      (node (ref "D12") (pin "14") (pinfunction "Boot_14") (pintype "passive"))
    )
    (net (code "29") (name "Net-(C267--)") (class "Default")
      (node (ref "C267") (pin "2") (pinfunction "-_2") (pintype "passive"))
      (node (ref "D12") (pin "12") (pinfunction "SW_12") (pintype "passive"))
      (node (ref "L9") (pin "1") (pinfunction "1_1") (pintype "passive"))
      (node (ref "R129") (pin "1") (pinfunction "+_1") (pintype "passive"))
    )
    (net (code "30") (name "Net-(C269-+)") (class "Default")
      (node (ref "C269") (pin "1") (pinfunction "+_1") (pintype "passive"))
      (node (ref "R164") (pin "1") (pinfunction "+_1") (pintype "passive"))
    )
    (net (code "31") (name "Net-(C269--)") (class "Default")
      (node (ref "C269") (pin "2") (pinfunction "-_2") (pintype "passive"))
      (node (ref "C97") (pin "1") (pinfunction "+_1") (pintype "passive"))
      (node (ref "C98") (pin "1") (pinfunction "+_1") (pintype "passive"))
      (node (ref "L12") (pin "2") (pinfunction "2_2") (pintype "passive"))
      (node (ref "R156") (pin "1") (pinfunction "+_1") (pintype "passive"))
      (node (ref "R158") (pin "1") (pinfunction "+_1") (pintype "passive"))
      (node (ref "R160") (pin "2") (pinfunction "-_2") (pintype "passive"))
      (node (ref "R161") (pin "2") (pinfunction "-_2") (pintype "passive"))
    )
    (net (code "32") (name "Net-(C270--)") (class "Default")
      (node (ref "C270") (pin "2") (pinfunction "-_2") (pintype "passive"))
      (node (ref "R165") (pin "2") (pinfunction "-_2") (pintype "passive"))
    )
    (net (code "33") (name "Net-(D12-Enable)") (class "Default")
      (node (ref "D12") (pin "15") (pinfunction "Enable_15") (pintype "passive"))
      (node (ref "R122") (pin "2") (pinfunction "-_2") (pintype "passive"))
      (node (ref "R124") (pin "2") (pinfunction "-_2") (pintype "passive"))
    )
    (net (code "34") (name "Net-(D12-OCSet)") (class "Default")
      (node (ref "D12") (pin "7") (pinfunction "OCSet_7") (pintype "passive"))
      (node (ref "R129") (pin "2") (pinfunction "-_2") (pintype "passive"))
    )
    (net (code "35") (name "Net-(D12-Rt)") (class "Default")
      (node (ref "D12") (pin "5") (pinfunction "Rt_5") (pintype "passive"))
      (node (ref "R132") (pin "1") (pinfunction "+_1") (pintype "passive"))
    )
    (net (code "36") (name "Net-(D12-Vsns)") (class "Default")
      (node (ref "D12") (pin "2") (pinfunction "Vsns_2") (pintype "passive"))
      (node (ref "R128") (pin "1") (pinfunction "+_1") (pintype "passive"))
      (node (ref "R142") (pin "2") (pinfunction "-_2") (pintype "passive"))
    )
    (net (code "37") (name "Net-(D13-FB1)") (class "Default")
      (node (ref "D13") (pin "12") (pinfunction "FB1_12") (pintype "passive"))
      (node (ref "R126") (pin "1") (pinfunction "+_1") (pintype "passive"))
      (node (ref "R127") (pin "2") (pinfunction "-_2") (pintype "passive"))
    )
    (net (code "38") (name "Net-(D13-FB2)") (class "Default")
      (node (ref "D13") (pin "16") (pinfunction "FB2_16") (pintype "passive"))
      (node (ref "R155") (pin "1") (pinfunction "+_1") (pintype "passive"))
      (node (ref "R157") (pin "2") (pinfunction "-_2") (pintype "passive"))
    )
    (net (code "39") (name "Net-(D13-LX1)") (class "Default")
      (node (ref "D13") (pin "7") (pinfunction "LX1_7") (pintype "passive"))
      (node (ref "L8") (pin "1") (pinfunction "1_1") (pintype "passive"))
    )
    (net (code "40") (name "Net-(D13-LX2-Pad5)") (class "Default")
      (node (ref "D13") (pin "5") (pinfunction "LX2_5") (pintype "passive"))
      (node (ref "D13") (pin "6") (pinfunction "LX2_6") (pintype "passive"))
      (node (ref "L11") (pin "1") (pinfunction "1_1") (pintype "passive"))
    )
    (net (code "41") (name "Net-(D14-OCSet)") (class "Default")
      (node (ref "D14") (pin "7") (pinfunction "OCSet_7") (pintype "passive"))
      (node (ref "R145") (pin "2") (pinfunction "-_2") (pintype "passive"))
    )
    (net (code "42") (name "Net-(D14-Rt)") (class "Default")
      (node (ref "D14") (pin "5") (pinfunction "Rt_5") (pintype "passive"))
      (node (ref "R162") (pin "1") (pinfunction "+_1") (pintype "passive"))
    )
    (net (code "43") (name "Net-(D14-Vsns)") (class "Default")
      (node (ref "D14") (pin "2") (pinfunction "Vsns_2") (pintype "passive"))
      (node (ref "R160") (pin "1") (pinfunction "+_1") (pintype "passive"))
      (node (ref "R167") (pin "2") (pinfunction "-_2") (pintype "passive"))
    )
    (net (code "44") (name "Net-(R131-+)") (class "Default")
      (node (ref "R131") (pin "1") (pinfunction "+_1") (pintype "passive"))
      (node (ref "R134") (pin "2") (pinfunction "-_2") (pintype "passive"))
      (node (ref "R135") (pin "1") (pinfunction "+_1") (pintype "passive"))
      (node (ref "R136") (pin "1") (pinfunction "+_1") (pintype "passive"))
      (node (ref "R139") (pin "2") (pinfunction "-_2") (pintype "passive"))
      (node (ref "R141") (pin "1") (pinfunction "+_1") (pintype "passive"))
    )
    (net (code "45") (name "Net-(R144-+)") (class "Default")
      (node (ref "R144") (pin "1") (pinfunction "+_1") (pintype "passive"))
      (node (ref "R148") (pin "1") (pinfunction "+_1") (pintype "passive"))
      (node (ref "R149") (pin "2") (pinfunction "-_2") (pintype "passive"))
      (node (ref "R152") (pin "2") (pinfunction "-_2") (pintype "passive"))
      (node (ref "R153") (pin "2") (pinfunction "-_2") (pintype "passive"))
    )
    (net (code "46") (name "VCC1P1") (class "Default")
      (node (ref "C100") (pin "1") (pinfunction "+_1") (pintype "passive"))
      (node (ref "C99") (pin "1") (pinfunction "+_1") (pintype "passive"))
      (node (ref "R156") (pin "2") (pinfunction "-_2") (pintype "passive"))
      (node (ref "R158") (pin "2") (pinfunction "-_2") (pintype "passive"))
    )
    (net (code "47") (name "VCC1P5_DDR3") (class "Default")
      (node (ref "R154") (pin "2") (pinfunction "-_2") (pintype "passive"))
    )
    (net (code "48") (name "VCC2P5") (class "Default")
      (node (ref "R123") (pin "2") (pinfunction "-_2") (pintype "passive"))
      (node (ref "R38") (pin "1") (pinfunction "+_1") (pintype "passive"))
    )
    (net (code "49") (name "VCC2P5_IO") (class "Default")
      (node (ref "R38") (pin "2") (pinfunction "-_2") (pintype "passive"))
    )
    (net (code "50") (name "VCC3P3") (class "Default")
      (node (ref "C268") (pin "1") (pinfunction "+_1") (pintype "passive"))
      (node (ref "C79") (pin "1") (pinfunction "+_1") (pintype "passive"))
      (node (ref "C80") (pin "1") (pinfunction "+_1") (pintype "passive"))
      (node (ref "C88") (pin "1") (pinfunction "+_1") (pintype "passive"))
      (node (ref "D13") (pin "10") (pinfunction "VDD_10") (pintype "passive"))
      (node (ref "D13") (pin "2") (pinfunction "PVDD2_2") (pintype "passive"))
      (node (ref "D13") (pin "3") (pinfunction "PVDD2_3") (pintype "passive"))
      (node (ref "D13") (pin "9") (pinfunction "PVDD1_9") (pintype "passive"))
      (node (ref "R121") (pin "2") (pinfunction "-_2") (pintype "passive"))
      (node (ref "R125") (pin "2") (pinfunction "-_2") (pintype "passive"))
      (node (ref "R131") (pin "2") (pinfunction "-_2") (pintype "passive"))
      (node (ref "R148") (pin "2") (pinfunction "-_2") (pintype "passive"))
      (node (ref "R36") (pin "1") (pinfunction "+_1") (pintype "passive"))
    )
    (net (code "51") (name "VCC3P3_IO") (class "Default")
      (node (ref "R36") (pin "2") (pinfunction "-_2") (pintype "passive"))
    )
    (net (code "52") (name "VIN") (class "Default")
      (node (ref "C68") (pin "1") (pinfunction "+_1") (pintype "passive"))
      (node (ref "C69") (pin "1") (pinfunction "+_1") (pintype "passive"))
      (node (ref "C75") (pin "1") (pinfunction "+_1") (pintype "passive"))
      (node (ref "C76") (pin "1") (pinfunction "+_1") (pintype "passive"))
      (node (ref "C89") (pin "1") (pinfunction "+_1") (pintype "passive"))
      (node (ref "C90") (pin "1") (pinfunction "+_1") (pintype "passive"))
      (node (ref "C95") (pin "1") (pinfunction "+_1") (pintype "passive"))
      (node (ref "C96") (pin "1") (pinfunction "+_1") (pintype "passive"))
      (node (ref "D12") (pin "13") (pinfunction "Vin_13") (pintype "passive"))
      (node (ref "D14") (pin "13") (pinfunction "Vin_13") (pintype "passive"))
      (node (ref "R122") (pin "1") (pinfunction "+_1") (pintype "passive"))
    )
    (net (code "53") (name "unconnected-(D12-Sync-Pad9)") (class "Default")
      (node (ref "D12") (pin "9") (pinfunction "Sync_9") (pintype "passive"))
    )
    (net (code "54") (name "unconnected-(D14-Sync-Pad9)") (class "Default")
      (node (ref "D14") (pin "9") (pinfunction "Sync_9") (pintype "passive"))
    )
  )
)
